# LDO_Schematic.net
KiCad netlist of a schematic drawn in Altium Designer
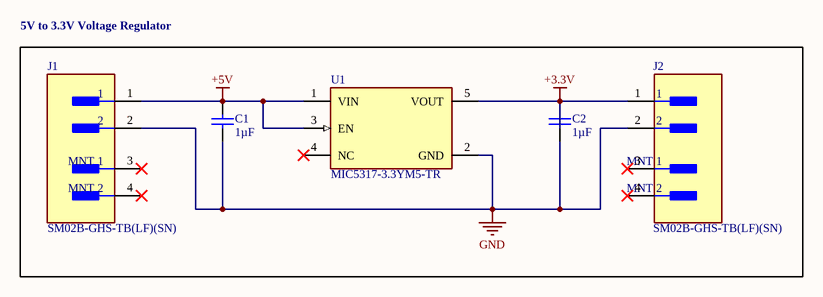
[diagram p0: LDO_Schematic.SchDoc]

(export (version "E")
  (design (tool "Eeschema 10.0.6"))
  (components
    (comp (ref "C1")
      (value "1µF")
      (footprint "CAPC2013X145X50NL20T20")
      (fields (field (name "PART NUMBER") "VJ0805Y105KXQRW1BC") (field (name "MANUFACTURER") "Vitramon"))
      (libsource (lib "Altium Content Vault") (part "CAP"))
    )
    (comp (ref "C2")
      (value "1µF")
      (footprint "CAPC2013X145X50NL20T20")
      (fields (field (name "PART NUMBER") "VJ0805Y105KXQRW1BC") (field (name "MANUFACTURER") "Vitramon"))
      (libsource (lib "Altium Content Vault") (part "CAP"))
    )
    (comp (ref "J1")
      (value "SM02B-GHS-TB(LF)(SN)")
      (footprint "FP-SM02B-GHS-TB_LF_SN-MFG")
      (description "CONN HEADER SMD R/A 2POS 1.25MM")
      (libsource (lib "") (part "56ec3178a87b3978bdc1b3682cd516a_1"))
    )
    (comp (ref "J2")
      (value "SM02B-GHS-TB(LF)(SN)")
      (footprint "FP-SM02B-GHS-TB_LF_SN-MFG")
      (description "CONN HEADER SMD R/A 2POS 1.25MM")
      (libsource (lib "Altium Content Vault") (part "56ec3178a87b3978bdc1b3682cd516a"))
    )
    (comp (ref "U1")
      (value "MIC5317-3.3YM5-TR")
      (footprint "FP-SOT23-5LD-PL-1-MFG")
      (description "IC REG LINEAR 3.3V 150MA SOT23-5")
      (libsource (lib "Altium Content Vault") (part "0a093dae7315cdc977fd108dde87457"))
    )
  )
  (nets
    (net (code "1") (name "+3.3V") (class "Default")
      (node (ref "C2") (pin "1") (pinfunction "1_1") (pintype "passive"))
      (node (ref "J2") (pin "1") (pinfunction "1_1") (pintype "passive"))
      (node (ref "U1") (pin "5") (pinfunction "VOUT_5") (pintype "power_in"))
    )
    (net (code "2") (name "+5V") (class "Default")
      (node (ref "C1") (pin "1") (pinfunction "1_1") (pintype "passive"))
      (node (ref "J1") (pin "1") (pinfunction "1_1") (pintype "passive"))
      (node (ref "U1") (pin "1") (pinfunction "VIN_1") (pintype "power_in"))
      (node (ref "U1") (pin "3") (pinfunction "EN_3") (pintype "input"))
    )
    (net (code "3") (name "GND") (class "Default")
      (node (ref "C1") (pin "2") (pinfunction "2_2") (pintype "passive"))
      (node (ref "C2") (pin "2") (pinfunction "2_2") (pintype "passive"))
      (node (ref "J1") (pin "2") (pinfunction "2_2") (pintype "passive"))
      (node (ref "J2") (pin "2") (pinfunction "2_2") (pintype "passive"))
      (node (ref "U1") (pin "2") (pinfunction "GND_2") (pintype "power_in"))
    )
    (net (code "4") (name "unconnected-(J1-MNT_1-Pad3)") (class "Default")
      (node (ref "J1") (pin "3") (pinfunction "MNT_1_3") (pintype "passive+no_connect"))
    )
    (net (code "5") (name "unconnected-(J1-MNT_2-Pad4)") (class "Default")
      (node (ref "J1") (pin "4") (pinfunction "MNT_2_4") (pintype "passive+no_connect"))
    )
    (net (code "6") (name "unconnected-(J2-MNT_1-Pad3)") (class "Default")
      (node (ref "J2") (pin "3") (pinfunction "MNT_1_3") (pintype "passive+no_connect"))
    )
    (net (code "7") (name "unconnected-(J2-MNT_2-Pad4)") (class "Default")
      (node (ref "J2") (pin "4") (pinfunction "MNT_2_4") (pintype "passive+no_connect"))
    )
    (net (code "8") (name "unconnected-(U1-NC-Pad4)") (class "Default")
      (node (ref "U1") (pin "4") (pinfunction "NC_4") (pintype "passive+no_connect"))
    )
  )
)
